# MidPower.net
KiCad netlist of a schematic drawn in Altium Designer
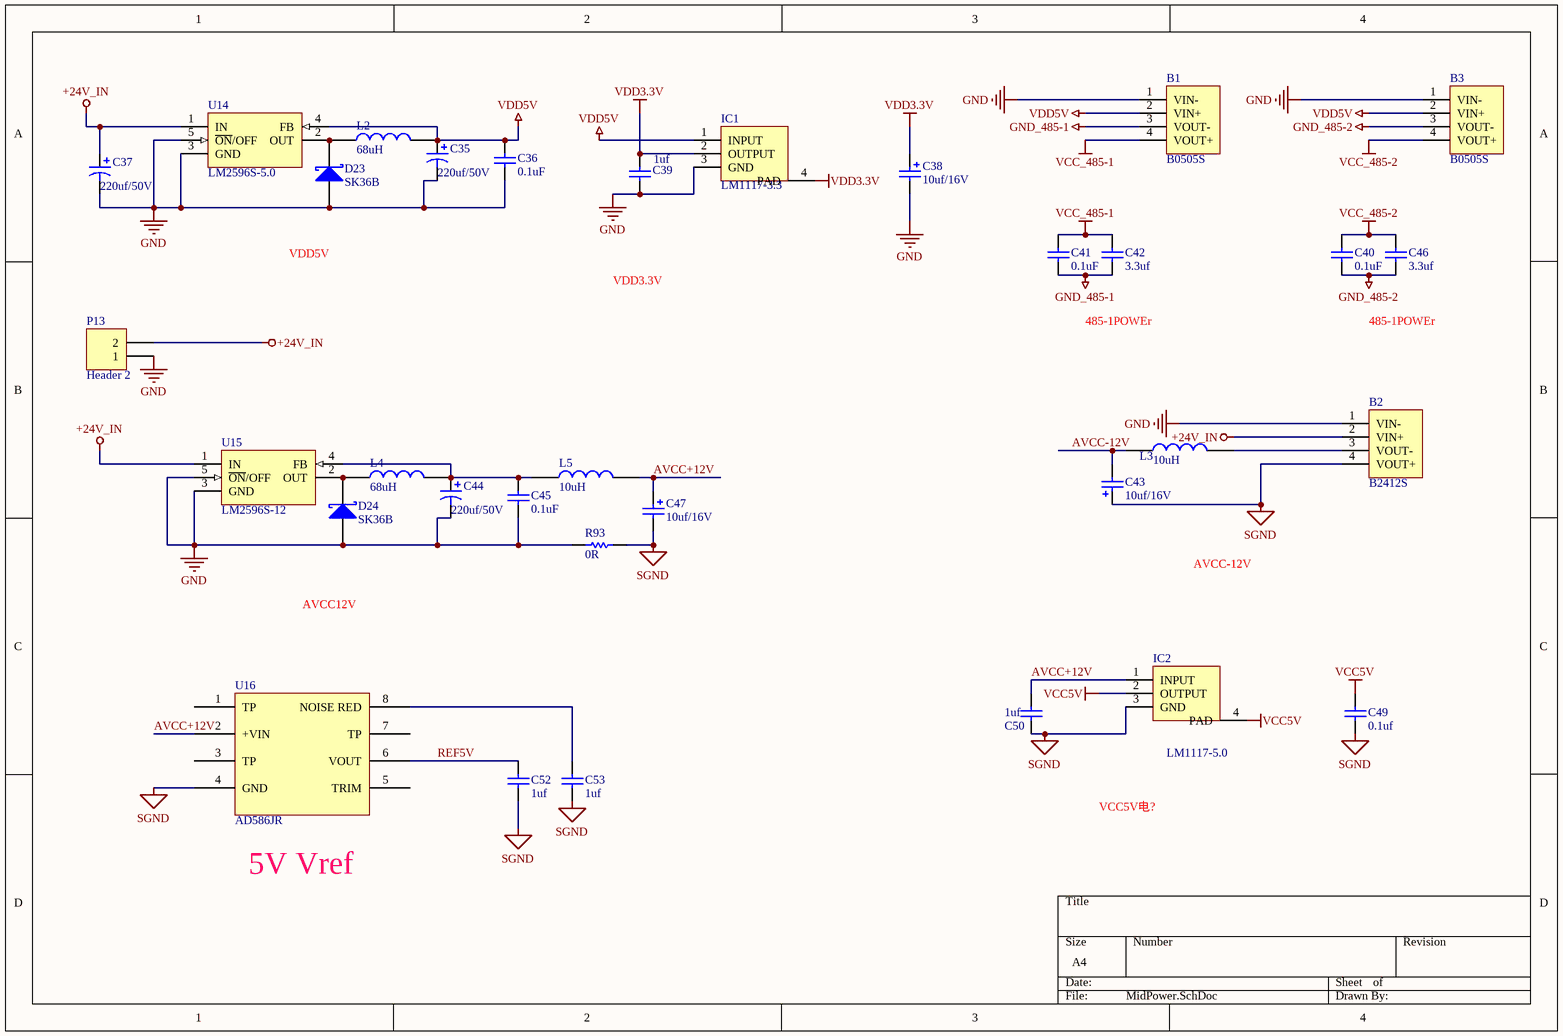
[diagram p0: MidPower.SchDoc]

(export (version "E")
  (design (tool "Eeschema 10.0.6"))
  (components
    (comp (ref "B1") (value "B0505S") (footprint "B0505S") (libsource (lib "S1") (part "B0505S")))
    (comp (ref "B2") (value "B2412S") (footprint "B0505S") (libsource (lib "S1") (part "B0505S")))
    (comp (ref "B3") (value "B0505S") (footprint "B0505S") (libsource (lib "S1") (part "B0505S")))
    (comp (ref "C35")
      (value "220uf/50V")
      (footprint "Cap5*10*12")
      (description "Polarized Capacitor (Radial)")
      (fields (field (name "Comment") "Cap Pol1") (field (name "PUBLISHER") "Altium Limited"))
      (libsource (lib "Miscellaneous Devices") (part "Cap Pol1"))
    )
    (comp (ref "C36")
      (value "0.1uF")
      (footprint "C0805")
      (description "Capacitor")
      (fields (field (name "Comment") "Cap") (field (name "PUBLISHER") "Altium Limited"))
      (libsource (lib "main board") (part "Cap_2"))
    )
    (comp (ref "C37")
      (value "220uf/50V")
      (footprint "Cap5*10*12")
      (description "Polarized Capacitor (Radial)")
      (fields (field (name "Comment") "Cap Pol1") (field (name "PUBLISHER") "Altium Limited"))
      (libsource (lib "Miscellaneous Devices") (part "Cap Pol1"))
    )
    (comp (ref "C38")
      (value "10uf/16V")
      (footprint "C3216")
      (description "Polarized Capacitor (Axial)")
      (fields (field (name "PUBLISHER") "Altium Limited"))
      (libsource (lib "Miscellaneous Devices") (part "Cap Pol2"))
    )
    (comp (ref "C39")
      (value "1uf")
      (footprint "C0805")
      (description "Capacitor")
      (fields
        (field (name "MANUFACTURER") "Generic Components")
        (field (name "Comment") "Cap")
        (field (name "PUBLISHER") "Altium Hobart Technology Centre")
      )
      (libsource (lib "Miscellaneous Devices") (part "Cap"))
    )
    (comp (ref "C40")
      (value "0.1uF")
      (footprint "C0805")
      (description "Capacitor")
      (fields (field (name "Comment") "Cap") (field (name "PUBLISHER") "Altium Limited"))
      (libsource (lib "main board") (part "Cap_2"))
    )
    (comp (ref "C41")
      (value "0.1uF")
      (footprint "C0805")
      (description "Capacitor")
      (fields (field (name "Comment") "Cap") (field (name "PUBLISHER") "Altium Limited"))
      (libsource (lib "main board") (part "Cap_2"))
    )
    (comp (ref "C42")
      (value "3.3uf")
      (footprint "C0805")
      (description "Capacitor")
      (fields (field (name "Comment") "Cap") (field (name "PUBLISHER") "Altium Limited"))
      (libsource (lib "main board") (part "Cap_2"))
    )
    (comp (ref "C43")
      (value "10uf/16V")
      (footprint "C3216")
      (description "Polarized Capacitor (Axial)")
      (fields (field (name "PUBLISHER") "Altium Limited"))
      (libsource (lib "Miscellaneous Devices") (part "Cap Pol2"))
    )
    (comp (ref "C44")
      (value "220uf/50V")
      (footprint "Cap5*10*12")
      (description "Polarized Capacitor (Radial)")
      (fields (field (name "Comment") "Cap Pol1") (field (name "PUBLISHER") "Altium Limited"))
      (libsource (lib "Miscellaneous Devices") (part "Cap Pol1"))
    )
    (comp (ref "C45")
      (value "0.1uF")
      (footprint "C0805")
      (description "Capacitor")
      (fields (field (name "Comment") "Cap") (field (name "PUBLISHER") "Altium Limited"))
      (libsource (lib "main board") (part "Cap_2"))
    )
    (comp (ref "C46")
      (value "3.3uf")
      (footprint "C0805")
      (description "Capacitor")
      (fields (field (name "Comment") "Cap") (field (name "PUBLISHER") "Altium Limited"))
      (libsource (lib "main board") (part "Cap_2"))
    )
    (comp (ref "C47")
      (value "10uf/16V")
      (footprint "C3216")
      (description "Polarized Capacitor (Axial)")
      (fields (field (name "PUBLISHER") "Altium Limited"))
      (libsource (lib "Miscellaneous Devices") (part "Cap Pol2"))
    )
    (comp (ref "C49")
      (value "0.1uf")
      (footprint "C0805")
      (description "Capacitor")
      (fields
        (field (name "MANUFACTURER") "Generic Components")
        (field (name "Comment") "Cap")
        (field (name "PUBLISHER") "Altium Hobart Technology Centre")
      )
      (libsource (lib "Miscellaneous Devices") (part "Cap"))
    )
    (comp (ref "C50")
      (value "1uf")
      (footprint "C0805")
      (description "Capacitor")
      (fields
        (field (name "MANUFACTURER") "Generic Components")
        (field (name "Comment") "Cap")
        (field (name "PUBLISHER") "Altium Hobart Technology Centre")
      )
      (libsource (lib "Miscellaneous Devices") (part "Cap"))
    )
    (comp (ref "C52")
      (value "1uf")
      (footprint "C0805")
      (description "Capacitor")
      (fields
        (field (name "MANUFACTURER") "Generic Components")
        (field (name "Comment") "Cap")
        (field (name "PUBLISHER") "Altium Hobart Technology Centre")
      )
      (libsource (lib "Miscellaneous Devices") (part "Cap"))
    )
    (comp (ref "C53")
      (value "1uf")
      (footprint "C0805")
      (description "Capacitor")
      (fields
        (field (name "MANUFACTURER") "Generic Components")
        (field (name "Comment") "Cap")
        (field (name "PUBLISHER") "Altium Hobart Technology Centre")
      )
      (libsource (lib "Miscellaneous Devices") (part "Cap"))
    )
    (comp (ref "D23")
      (value "SK36B")
      (footprint "SMB")
      (description "Schottky Diode")
      (fields (field (name "PUBLISHER") "Altium Limited"))
      (libsource (lib "Miscellaneous Devices") (part "D Schottky"))
    )
    (comp (ref "D24")
      (value "SK36B")
      (footprint "SMB")
      (description "Schottky Diode")
      (fields (field (name "PUBLISHER") "Altium Limited"))
      (libsource (lib "Miscellaneous Devices") (part "D Schottky"))
    )
    (comp (ref "IC1") (value "LM1117-3.3") (footprint "LM1117") (libsource (lib "S1") (part "LM1117")))
    (comp (ref "IC2") (value "LM1117-5.0") (footprint "LM1117") (libsource (lib "S1") (part "LM1117")))
    (comp (ref "L2") (value "68uH") (footprint "IND_HM00_12*12") (libsource (lib "电源板") (part "INDUCTOR")))
    (comp (ref "L3") (value "10uH") (footprint "INDM4532N") (libsource (lib "电源板") (part "INDUCTOR")))
    (comp (ref "L4") (value "68uH") (footprint "IND_HM00_12*12") (libsource (lib "电源板") (part "INDUCTOR")))
    (comp (ref "L5") (value "10uH") (footprint "INDM4532N") (libsource (lib "电源板") (part "INDUCTOR")))
    (comp (ref "P13")
      (value "Header 2")
      (footprint "3.5-P2")
      (description "Header, 2-Pin")
      (fields (field (name "PUBLISHER") "Altium Limited"))
      (libsource (lib "Miscellaneous Connectors") (part "Header 2"))
    )
    (comp (ref "R93")
      (value "0R")
      (footprint "0805")
      (description "Semiconductor Resistor")
      (fields (field (name "Comment") "Res Semi") (field (name "PUBLISHER") "Altium Limited"))
      (libsource (lib "Miscellaneous Devices") (part "Res Semi"))
    )
    (comp (ref "U14")
      (value "LM2596S-5.0")
      (footprint "TS5B_M")
      (description "Simple Switcher Power Converter 150 kHz 3A Step Down Voltage Regulator")
      (fields (field (name "PUBLISHER") "Altium Limited"))
      (libsource (lib "NSC Power Mgt Switching Regulator") (part "LM2596S-5.0"))
    )
    (comp (ref "U15")
      (value "LM2596S-12")
      (footprint "TS5B_M")
      (description "Simple Switcher Power Converter 150 kHz 3A Step Down Voltage Regulator")
      (fields (field (name "PUBLISHER") "Altium Limited"))
      (libsource (lib "NSC Power Mgt Switching Regulator") (part "LM2596S-12"))
    )
    (comp (ref "U16") (value "AD586JR") (footprint "SOP8_M") (libsource (lib "斜测仪") (part "AD586L")))
  )
  (nets
    (net (code "1") (name "+24V_IN") (class "Default")
      (node (ref "B2") (pin "2") (pinfunction "VIN+_2") (pintype "passive"))
      (node (ref "C37") (pin "1") (pinfunction "1_1") (pintype "passive"))
      (node (ref "P13") (pin "2") (pinfunction "2_2") (pintype "passive"))
      (node (ref "U14") (pin "1") (pinfunction "IN_1") (pintype "power_in"))
      (node (ref "U15") (pin "1") (pinfunction "IN_1") (pintype "power_in"))
    )
    (net (code "2") (name "/AVCC+12V") (class "Default")
      (node (ref "C47") (pin "1") (pinfunction "1_1") (pintype "passive"))
      (node (ref "C50") (pin "1") (pinfunction "1_1") (pintype "passive"))
      (node (ref "IC2") (pin "1") (pinfunction "INPUT_1") (pintype "passive"))
      (node (ref "L5") (pin "2") (pinfunction "2_2") (pintype "passive"))
      (node (ref "U16") (pin "2") (pinfunction "+VIN_2") (pintype "passive"))
    )
    (net (code "3") (name "/AVCC-12V") (class "Default")
      (node (ref "C43") (pin "2") (pinfunction "2_2") (pintype "passive"))
      (node (ref "L3") (pin "1") (pinfunction "1_1") (pintype "passive"))
    )
    (net (code "4") (name "/REF5V") (class "Default")
      (node (ref "C52") (pin "1") (pinfunction "1_1") (pintype "passive"))
      (node (ref "U16") (pin "6") (pinfunction "VOUT_6") (pintype "passive"))
    )
    (net (code "5") (name "GND") (class "Default")
      (node (ref "B1") (pin "1") (pinfunction "VIN-_1") (pintype "passive"))
      (node (ref "B2") (pin "1") (pinfunction "VIN-_1") (pintype "passive"))
      (node (ref "B3") (pin "1") (pinfunction "VIN-_1") (pintype "passive"))
      (node (ref "C35") (pin "2") (pinfunction "2_2") (pintype "passive"))
      (node (ref "C36") (pin "1") (pinfunction "1_1") (pintype "passive"))
      (node (ref "C37") (pin "2") (pinfunction "2_2") (pintype "passive"))
      (node (ref "C38") (pin "2") (pinfunction "2_2") (pintype "passive"))
      (node (ref "C39") (pin "2") (pinfunction "2_2") (pintype "passive"))
      (node (ref "C44") (pin "2") (pinfunction "2_2") (pintype "passive"))
      (node (ref "C45") (pin "1") (pinfunction "1_1") (pintype "passive"))
      (node (ref "D23") (pin "1") (pinfunction "A_1") (pintype "passive"))
      (node (ref "D24") (pin "1") (pinfunction "A_1") (pintype "passive"))
      (node (ref "IC1") (pin "3") (pinfunction "GND_3") (pintype "passive"))
      (node (ref "P13") (pin "1") (pinfunction "1_1") (pintype "passive"))
      (node (ref "R93") (pin "2") (pinfunction "2_2") (pintype "passive"))
      (node (ref "U14") (pin "3") (pinfunction "GND_3") (pintype "power_in"))
      (node (ref "U14") (pin "5") (pinfunction "~{ON}/OFF_5") (pintype "input"))
      (node (ref "U15") (pin "3") (pinfunction "GND_3") (pintype "power_in"))
      (node (ref "U15") (pin "5") (pinfunction "~{ON}/OFF_5") (pintype "input"))
    )
    (net (code "6") (name "GND_485-1") (class "Default")
      (node (ref "B1") (pin "3") (pinfunction "VOUT-_3") (pintype "passive"))
      (node (ref "C41") (pin "1") (pinfunction "1_1") (pintype "passive"))
      (node (ref "C42") (pin "1") (pinfunction "1_1") (pintype "passive"))
    )
    (net (code "7") (name "GND_485-2") (class "Default")
      (node (ref "B3") (pin "3") (pinfunction "VOUT-_3") (pintype "passive"))
      (node (ref "C40") (pin "1") (pinfunction "1_1") (pintype "passive"))
      (node (ref "C46") (pin "1") (pinfunction "1_1") (pintype "passive"))
    )
    (net (code "8") (name "Net-(B2-VOUT-)") (class "Default")
      (node (ref "B2") (pin "3") (pinfunction "VOUT-_3") (pintype "passive"))
      (node (ref "L3") (pin "2") (pinfunction "2_2") (pintype "passive"))
    )
    (net (code "9") (name "Net-(D23-K)") (class "Default")
      (node (ref "D23") (pin "2") (pinfunction "K_2") (pintype "passive"))
      (node (ref "L2") (pin "1") (pinfunction "1_1") (pintype "passive"))
      (node (ref "U14") (pin "2") (pinfunction "OUT_2") (pintype "power_in"))
    )
    (net (code "10") (name "Net-(D24-K)") (class "Default")
      (node (ref "D24") (pin "2") (pinfunction "K_2") (pintype "passive"))
      (node (ref "L4") (pin "1") (pinfunction "1_1") (pintype "passive"))
      (node (ref "U15") (pin "2") (pinfunction "OUT_2") (pintype "power_in"))
    )
    (net (code "11") (name "Net-(U15-FB)") (class "Default")
      (node (ref "C44") (pin "1") (pinfunction "1_1") (pintype "passive"))
      (node (ref "C45") (pin "2") (pinfunction "2_2") (pintype "passive"))
      (node (ref "L4") (pin "2") (pinfunction "2_2") (pintype "passive"))
      (node (ref "L5") (pin "1") (pinfunction "1_1") (pintype "passive"))
      (node (ref "U15") (pin "4") (pinfunction "FB_4") (pintype "input"))
    )
    (net (code "12") (name "Net-(U16-NOISE_RED)") (class "Default")
      (node (ref "C53") (pin "1") (pinfunction "1_1") (pintype "passive"))
      (node (ref "U16") (pin "8") (pinfunction "NOISE_RED_8") (pintype "passive"))
    )
    (net (code "13") (name "SGND") (class "Default")
      (node (ref "B2") (pin "4") (pinfunction "VOUT+_4") (pintype "passive"))
      (node (ref "C43") (pin "1") (pinfunction "1_1") (pintype "passive"))
      (node (ref "C47") (pin "2") (pinfunction "2_2") (pintype "passive"))
      (node (ref "C49") (pin "2") (pinfunction "2_2") (pintype "passive"))
      (node (ref "C50") (pin "2") (pinfunction "2_2") (pintype "passive"))
      (node (ref "C52") (pin "2") (pinfunction "2_2") (pintype "passive"))
      (node (ref "C53") (pin "2") (pinfunction "2_2") (pintype "passive"))
      (node (ref "IC2") (pin "3") (pinfunction "GND_3") (pintype "passive"))
      (node (ref "R93") (pin "1") (pinfunction "1_1") (pintype "passive"))
      (node (ref "U16") (pin "4") (pinfunction "GND_4") (pintype "passive"))
    )
    (net (code "14") (name "VCC5V") (class "Default")
      (node (ref "C49") (pin "1") (pinfunction "1_1") (pintype "passive"))
      (node (ref "IC2") (pin "2") (pinfunction "OUTPUT_2") (pintype "passive"))
      (node (ref "IC2") (pin "4") (pinfunction "PAD_4") (pintype "passive"))
    )
    (net (code "15") (name "VCC_485-1") (class "Default")
      (node (ref "B1") (pin "4") (pinfunction "VOUT+_4") (pintype "passive"))
      (node (ref "C41") (pin "2") (pinfunction "2_2") (pintype "passive"))
      (node (ref "C42") (pin "2") (pinfunction "2_2") (pintype "passive"))
    )
    (net (code "16") (name "VCC_485-2") (class "Default")
      (node (ref "B3") (pin "4") (pinfunction "VOUT+_4") (pintype "passive"))
      (node (ref "C40") (pin "2") (pinfunction "2_2") (pintype "passive"))
      (node (ref "C46") (pin "2") (pinfunction "2_2") (pintype "passive"))
    )
    (net (code "17") (name "VDD3.3V") (class "Default")
      (node (ref "C38") (pin "1") (pinfunction "1_1") (pintype "passive"))
      (node (ref "C39") (pin "1") (pinfunction "1_1") (pintype "passive"))
      (node (ref "IC1") (pin "2") (pinfunction "OUTPUT_2") (pintype "passive"))
      (node (ref "IC1") (pin "4") (pinfunction "PAD_4") (pintype "passive"))
    )
    (net (code "18") (name "VDD5V") (class "Default")
      (node (ref "B1") (pin "2") (pinfunction "VIN+_2") (pintype "passive"))
      (node (ref "B3") (pin "2") (pinfunction "VIN+_2") (pintype "passive"))
      (node (ref "C35") (pin "1") (pinfunction "1_1") (pintype "passive"))
      (node (ref "C36") (pin "2") (pinfunction "2_2") (pintype "passive"))
      (node (ref "IC1") (pin "1") (pinfunction "INPUT_1") (pintype "passive"))
      (node (ref "L2") (pin "2") (pinfunction "2_2") (pintype "passive"))
      (node (ref "U14") (pin "4") (pinfunction "FB_4") (pintype "input"))
    )
    (net (code "19") (name "unconnected-(U16-TP-Pad1)") (class "Default")
      (node (ref "U16") (pin "1") (pinfunction "TP_1") (pintype "passive"))
    )
    (net (code "20") (name "unconnected-(U16-TP-Pad3)") (class "Default")
      (node (ref "U16") (pin "3") (pinfunction "TP_3") (pintype "passive"))
    )
    (net (code "21") (name "unconnected-(U16-TP-Pad7)") (class "Default")
      (node (ref "U16") (pin "7") (pinfunction "TP_7") (pintype "passive"))
    )
    (net (code "22") (name "unconnected-(U16-TRIM-Pad5)") (class "Default")
      (node (ref "U16") (pin "5") (pinfunction "TRIM_5") (pintype "passive"))
    )
  )
)
